# H_BRIGGE_1.net
KiCad netlist of a schematic drawn in Altium Designer
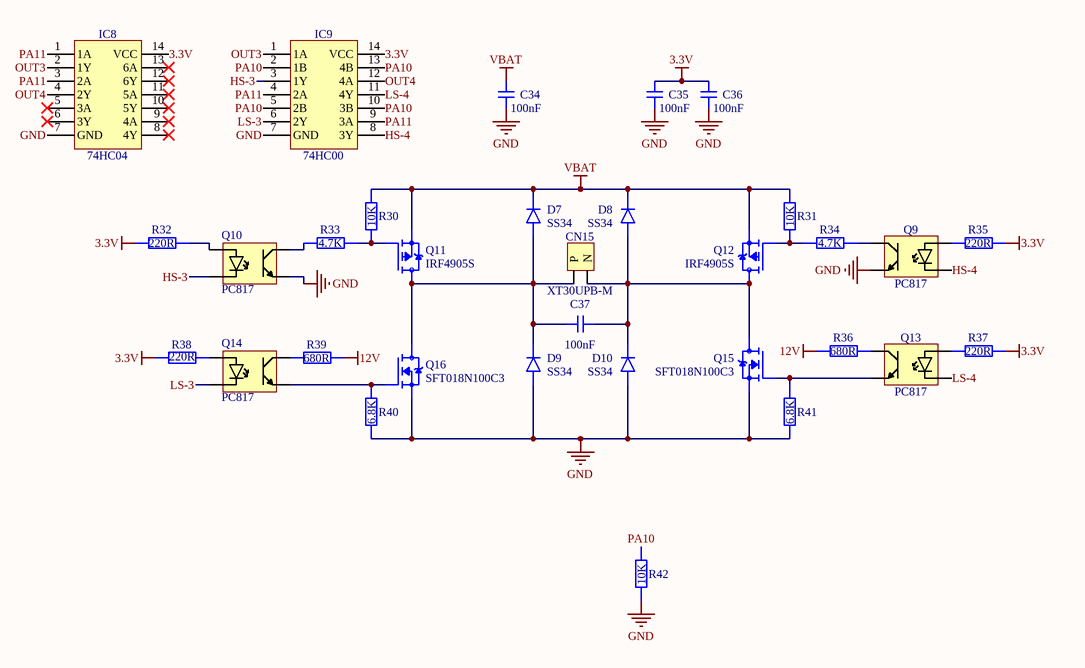
[diagram p0: H_BRIGGE_1.SchDoc]

(export (version "E")
  (design (tool "Eeschema 10.0.6"))
  (components
    (comp (ref "C34")
      (value "100nF")
      (footprint "CAP-0603-2")
      (description "100nF ±10% 50V Ceramic Capacitor X7R 0603")
      (fields (field (name "MANUFACTURER") "Samsung Electro-Mechanics") (field (name "LCSC PART #") "C1591"))
      (libsource (lib "CbyP") (part "CL10B104KB8NNNC"))
    )
    (comp (ref "C35")
      (value "100nF")
      (footprint "CAP-0603-2")
      (description "100nF ±10% 50V Ceramic Capacitor X7R 0603")
      (fields (field (name "MANUFACTURER") "Samsung Electro-Mechanics") (field (name "LCSC PART #") "C1591"))
      (libsource (lib "CbyP") (part "CL10B104KB8NNNC"))
    )
    (comp (ref "C36")
      (value "100nF")
      (footprint "CAP-0603-2")
      (description "100nF ±10% 50V Ceramic Capacitor X7R 0603")
      (fields (field (name "MANUFACTURER") "Samsung Electro-Mechanics") (field (name "LCSC PART #") "C1591"))
      (libsource (lib "CbyP") (part "CL10B104KB8NNNC"))
    )
    (comp (ref "C37")
      (value "100nF")
      (footprint "CAP-0603-2")
      (description "100nF ±10% 50V Ceramic Capacitor X7R 0603")
      (fields (field (name "MANUFACTURER") "Samsung Electro-Mechanics") (field (name "LCSC PART #") "C1591"))
      (libsource (lib "CbyP") (part "CL10B104KB8NNNC"))
    )
    (comp (ref "CN15")
      (value "XT30UPB-M")
      (footprint "XT30UPB-M")
      (description "Banana and Tip Connector Adapters")
      (fields
        (field (name "MANUFACTURER") "Changzhou Amass Elec")
        (field (name "MFR.PART #") "XT30PW-M30.G.Y")
      )
      (libsource (lib "CbyP") (part "XT30UPB-M"))
    )
    (comp (ref "D7")
      (value "SS34")
      (footprint "SMA(DO-214AC)")
      (description "Diode Independent 40V 3A Surface Mount SMA(DO-214AC)")
      (fields (field (name "MANUFACTURER") "GOODWORK") (field (name "LCSC PART #") "C908680"))
      (libsource (lib "CbyP") (part "SS34"))
    )
    (comp (ref "D8")
      (value "SS34")
      (footprint "SMA(DO-214AC)")
      (description "Diode Independent 40V 3A Surface Mount SMA(DO-214AC)")
      (fields (field (name "MANUFACTURER") "GOODWORK") (field (name "LCSC PART #") "C908680"))
      (libsource (lib "CbyP") (part "SS34"))
    )
    (comp (ref "D9")
      (value "SS34")
      (footprint "SMA(DO-214AC)")
      (description "Diode Independent 40V 3A Surface Mount SMA(DO-214AC)")
      (fields (field (name "MANUFACTURER") "GOODWORK") (field (name "LCSC PART #") "C908680"))
      (libsource (lib "CbyP") (part "SS34"))
    )
    (comp (ref "D10")
      (value "SS34")
      (footprint "SMA(DO-214AC)")
      (description "Diode Independent 40V 3A Surface Mount SMA(DO-214AC)")
      (fields (field (name "MANUFACTURER") "GOODWORK") (field (name "LCSC PART #") "C908680"))
      (libsource (lib "CbyP") (part "SS34"))
    )
    (comp (ref "IC8")
      (value "74HC04")
      (footprint "SOP-14")
      (description "2V~6V 16ns@6V,50pF 2uA 6 1 SOIC-14 Gates and Inverters RoHS")
      (fields (field (name "MANUFACTURER") "TI") (field (name "MFR.PART #") "SN74HC04DR"))
      (libsource (lib "CbyP") (part "SN74HC04DR"))
    )
    (comp (ref "IC9")
      (value "74HC00")
      (footprint "SOP-14")
      (description "2uA 2V~6V 15ns@6V,50pF SOIC-14 Gates and Inverters RoHS")
      (fields (field (name "MANUFACTURER") "TI") (field (name "MFR.PART #") "SN74HC00DR"))
      (libsource (lib "CbyP") (part "SN74HC00DR"))
    )
    (comp (ref "Q9")
      (value "PC817")
      (footprint "SOP-4")
      (description "Phototransistor Output 5kVrms 1 Channel SOP-4-2.54mm")
      (fields (field (name "MANUFACTURER") "UMW") (field (name "MFR.PART #") "PC817C-S"))
      (libsource (lib "CbyP") (part "PC817C-S"))
    )
    (comp (ref "Q10")
      (value "PC817")
      (footprint "SOP-4")
      (description "Phototransistor Output 5kVrms 1 Channel SOP-4-2.54mm")
      (fields (field (name "MANUFACTURER") "UMW") (field (name "MFR.PART #") "PC817C-S"))
      (libsource (lib "XE_BIA") (part "PC817C-S"))
    )
    (comp (ref "Q11")
      (value "IRF4905S")
      (footprint "TO-263")
      (description "P-Channel 55V 70A 170W Surface Mount D2PAK")
      (fields (field (name "MANUFACTURER") "Infineon") (field (name "MFR.PART #") "IRF4905STRLPBF"))
      (libsource (lib "CbyP") (part "IRF4905STRLPBF"))
    )
    (comp (ref "Q12")
      (value "IRF4905S")
      (footprint "TO-263")
      (description "P-Channel 55V 70A 170W Surface Mount D2PAK")
      (fields (field (name "MANUFACTURER") "Infineon") (field (name "MFR.PART #") "IRF4905STRLPBF"))
      (libsource (lib "CbyP") (part "IRF4905STRLPBF"))
    )
    (comp (ref "Q13")
      (value "PC817")
      (footprint "SOP-4")
      (description "Phototransistor Output 5kVrms 1 Channel SOP-4-2.54mm")
      (fields (field (name "MANUFACTURER") "UMW") (field (name "MFR.PART #") "PC817C-S"))
      (libsource (lib "CbyP") (part "PC817C-S"))
    )
    (comp (ref "Q14")
      (value "PC817")
      (footprint "SOP-4")
      (description "Phototransistor Output 5kVrms 1 Channel SOP-4-2.54mm")
      (fields (field (name "MANUFACTURER") "UMW") (field (name "MFR.PART #") "PC817C-S"))
      (libsource (lib "XE_BIA") (part "PC817C-S"))
    )
    (comp (ref "Q15")
      (value "SFT018N100C3")
      (footprint "TOLL")
      (description "N-Channel 100V 320A 312W Surface Mount TOLL")
      (fields (field (name "MANUFACTURER") "SCILICON") (field (name "LCSC PART #") "C42395330"))
      (libsource (lib "CbyP") (part "SFT018N100C3"))
    )
    (comp (ref "Q16")
      (value "SFT018N100C3")
      (footprint "TOLL")
      (description "N-Channel 100V 320A 312W Surface Mount TOLL")
      (fields (field (name "MANUFACTURER") "SCILICON") (field (name "LCSC PART #") "C42395330"))
      (libsource (lib "CbyP") (part "SFT018N100C3"))
    )
    (comp (ref "R30")
      (value "10K")
      (footprint "RES-0603-1")
      (description "100mW 10kΩ 75V Thick Film Resistor ±100ppm/℃ ±1% 0603 Chip Resistor - Surface Mount RoHS")
      (fields (field (name "MANUFACTURER") "YAGEO") (field (name "LCSC PART #") "C98220"))
      (libsource (lib "CbyP") (part "RC0603FR-0710KL"))
    )
    (comp (ref "R31")
      (value "10K")
      (footprint "RES-0603-1")
      (description "100mW 10kΩ 75V Thick Film Resistor ±100ppm/℃ ±1% 0603 Chip Resistor - Surface Mount RoHS")
      (fields (field (name "MANUFACTURER") "YAGEO") (field (name "LCSC PART #") "C98220"))
      (libsource (lib "CbyP") (part "RC0603FR-0710KL"))
    )
    (comp (ref "R32")
      (value "220R")
      (footprint "RES-0603-1")
      (description "220Ω ±1% 100mW 0603 Thick Film Resistor")
      (fields (field (name "MANUFACTURER") "UNI-ROYAL") (field (name "MFR.PART #") "0603WAF2200T5E"))
      (libsource (lib "CbyP") (part "0603WAF2200T5E"))
    )
    (comp (ref "R33")
      (value "4.7K")
      (footprint "RES-0603-1")
      (description "100mW 4.7kΩ 75V Thick Film Resistor ±100ppm/℃ ±1% 0603 Chip Resistor - Surface Mount RoHS")
      (fields (field (name "MANUFACTURER") "YAGEO") (field (name "MFR.PART #") "RC0603FR-074K7L"))
      (libsource (lib "CbyP") (part "RC0603FR-074K7L"))
    )
    (comp (ref "R34")
      (value "4.7K")
      (footprint "RES-0603-1")
      (description "100mW 4.7kΩ 75V Thick Film Resistor ±100ppm/℃ ±1% 0603 Chip Resistor - Surface Mount RoHS")
      (fields (field (name "MANUFACTURER") "YAGEO") (field (name "MFR.PART #") "RC0603FR-074K7L"))
      (libsource (lib "CbyP") (part "RC0603FR-074K7L"))
    )
    (comp (ref "R35")
      (value "220R")
      (footprint "RES-0603-1")
      (description "220Ω ±1% 100mW 0603 Thick Film Resistor")
      (fields (field (name "MANUFACTURER") "UNI-ROYAL") (field (name "MFR.PART #") "0603WAF2200T5E"))
      (libsource (lib "CbyP") (part "0603WAF2200T5E"))
    )
    (comp (ref "R36")
      (value "680R")
      (footprint "RES-0603-1")
      (description "680Ω ±1% 100mW 0603 Thick Film Resistor")
      (fields (field (name "MANUFACTURER") "FOJAN") (field (name "MFR.PART #") "FRC0603F6800TS"))
      (libsource (lib "CbyP") (part "FRC0603F6800TS"))
    )
    (comp (ref "R37")
      (value "220R")
      (footprint "RES-0603-1")
      (description "220Ω ±1% 100mW 0603 Thick Film Resistor")
      (fields (field (name "MANUFACTURER") "UNI-ROYAL") (field (name "MFR.PART #") "0603WAF2200T5E"))
      (libsource (lib "CbyP") (part "0603WAF2200T5E"))
    )
    (comp (ref "R38")
      (value "220R")
      (footprint "RES-0603-1")
      (description "220Ω ±1% 100mW 0603 Thick Film Resistor")
      (fields (field (name "MANUFACTURER") "UNI-ROYAL") (field (name "MFR.PART #") "0603WAF2200T5E"))
      (libsource (lib "CbyP") (part "0603WAF2200T5E"))
    )
    (comp (ref "R39")
      (value "680R")
      (footprint "RES-0603-1")
      (description "680Ω ±1% 100mW 0603 Thick Film Resistor")
      (fields (field (name "MANUFACTURER") "FOJAN") (field (name "MFR.PART #") "FRC0603F6800TS"))
      (libsource (lib "CbyP") (part "FRC0603F6800TS"))
    )
    (comp (ref "R40")
      (value "6.8K")
      (footprint "RES-0603-1")
      (description "6.8kΩ ±1% 100mW 0603 Thick Film Resistor")
      (fields (field (name "MANUFACTURER") "UNI-ROYAL") (field (name "MFR.PART #") "0603WAF6801T5E"))
      (libsource (lib "CbyP") (part "0603WAF6801T5E"))
    )
    (comp (ref "R41")
      (value "6.8K")
      (footprint "RES-0603-1")
      (description "6.8kΩ ±1% 100mW 0603 Thick Film Resistor")
      (fields (field (name "MANUFACTURER") "UNI-ROYAL") (field (name "MFR.PART #") "0603WAF6801T5E"))
      (libsource (lib "CbyP") (part "0603WAF6801T5E"))
    )
    (comp (ref "R42")
      (value "10K")
      (footprint "RES-0603-1")
      (description "100mW 10kΩ 75V Thick Film Resistor ±100ppm/℃ ±1% 0603 Chip Resistor - Surface Mount RoHS")
      (fields (field (name "MANUFACTURER") "YAGEO") (field (name "LCSC PART #") "C98220"))
      (libsource (lib "CbyP") (part "RC0603FR-0710KL"))
    )
  )
  (nets
    (net (code "1") (name "/HS-3") (class "Default")
      (node (ref "IC9") (pin "3") (pinfunction "1Y_3") (pintype "passive"))
      (node (ref "Q10") (pin "2") (pinfunction "K_2") (pintype "passive"))
    )
    (net (code "2") (name "/HS-4") (class "Default")
      (node (ref "IC9") (pin "8") (pinfunction "3Y_8") (pintype "passive"))
      (node (ref "Q9") (pin "2") (pinfunction "K_2") (pintype "passive"))
    )
    (net (code "3") (name "/LS-3") (class "Default")
      (node (ref "IC9") (pin "6") (pinfunction "2Y_6") (pintype "passive"))
      (node (ref "Q14") (pin "2") (pinfunction "K_2") (pintype "passive"))
    )
    (net (code "4") (name "/LS-4") (class "Default")
      (node (ref "IC9") (pin "11") (pinfunction "4Y_11") (pintype "passive"))
      (node (ref "Q13") (pin "2") (pinfunction "K_2") (pintype "passive"))
    )
    (net (code "5") (name "/OUT3") (class "Default")
      (node (ref "IC8") (pin "2") (pinfunction "1Y_2") (pintype "passive"))
      (node (ref "IC9") (pin "1") (pinfunction "1A_1") (pintype "passive"))
    )
    (net (code "6") (name "/OUT4") (class "Default")
      (node (ref "IC8") (pin "4") (pinfunction "2Y_4") (pintype "passive"))
      (node (ref "IC9") (pin "12") (pinfunction "4A_12") (pintype "passive"))
    )
    (net (code "7") (name "/PA10") (class "Default")
      (node (ref "IC9") (pin "10") (pinfunction "3B_10") (pintype "passive"))
      (node (ref "IC9") (pin "13") (pinfunction "4B_13") (pintype "passive"))
      (node (ref "IC9") (pin "2") (pinfunction "1B_2") (pintype "passive"))
      (node (ref "IC9") (pin "5") (pinfunction "2B_5") (pintype "passive"))
      (node (ref "R42") (pin "2") (pinfunction "2_2") (pintype "passive"))
    )
    (net (code "8") (name "/PA11") (class "Default")
      (node (ref "IC8") (pin "1") (pinfunction "1A_1") (pintype "passive"))
      (node (ref "IC8") (pin "3") (pinfunction "2A_3") (pintype "passive"))
      (node (ref "IC9") (pin "4") (pinfunction "2A_4") (pintype "passive"))
      (node (ref "IC9") (pin "9") (pinfunction "3A_9") (pintype "passive"))
    )
    (net (code "9") (name "3.3V") (class "Default")
      (node (ref "C35") (pin "1") (pinfunction "1_1") (pintype "passive"))
      (node (ref "C36") (pin "1") (pinfunction "1_1") (pintype "passive"))
      (node (ref "IC8") (pin "14") (pinfunction "VCC_14") (pintype "passive"))
      (node (ref "IC9") (pin "14") (pinfunction "VCC_14") (pintype "passive"))
      (node (ref "R32") (pin "2") (pinfunction "2_2") (pintype "passive"))
      (node (ref "R35") (pin "1") (pinfunction "1_1") (pintype "passive"))
      (node (ref "R37") (pin "1") (pinfunction "1_1") (pintype "passive"))
      (node (ref "R38") (pin "2") (pinfunction "2_2") (pintype "passive"))
    )
    (net (code "10") (name "12V") (class "Default")
      (node (ref "R36") (pin "2") (pinfunction "2_2") (pintype "passive"))
      (node (ref "R39") (pin "2") (pinfunction "2_2") (pintype "passive"))
    )
    (net (code "11") (name "GND") (class "Default")
      (node (ref "C34") (pin "2") (pinfunction "2_2") (pintype "passive"))
      (node (ref "C35") (pin "2") (pinfunction "2_2") (pintype "passive"))
      (node (ref "C36") (pin "2") (pinfunction "2_2") (pintype "passive"))
      (node (ref "D10") (pin "1") (pinfunction "A_1") (pintype "passive"))
      (node (ref "D9") (pin "1") (pinfunction "A_1") (pintype "passive"))
      (node (ref "IC8") (pin "7") (pinfunction "GND_7") (pintype "passive"))
      (node (ref "IC9") (pin "7") (pinfunction "GND_7") (pintype "passive"))
      (node (ref "Q10") (pin "3") (pinfunction "E_3") (pintype "passive"))
      (node (ref "Q15") (pin "2") (pinfunction "S_2") (pintype "passive"))
      (node (ref "Q16") (pin "2") (pinfunction "S_2") (pintype "passive"))
      (node (ref "Q9") (pin "3") (pinfunction "E_3") (pintype "passive"))
      (node (ref "R40") (pin "1") (pinfunction "1_1") (pintype "passive"))
      (node (ref "R41") (pin "1") (pinfunction "1_1") (pintype "passive"))
      (node (ref "R42") (pin "1") (pinfunction "1_1") (pintype "passive"))
    )
    (net (code "12") (name "Net-(CN15-N)") (class "Default")
      (node (ref "C37") (pin "1") (pinfunction "1_1") (pintype "passive"))
      (node (ref "CN15") (pin "2") (pinfunction "N_2") (pintype "passive"))
      (node (ref "D10") (pin "2") (pinfunction "K_2") (pintype "passive"))
      (node (ref "D8") (pin "1") (pinfunction "A_1") (pintype "passive"))
      (node (ref "Q12") (pin "2") (pinfunction "D_2") (pintype "passive"))
      (node (ref "Q15") (pin "3") (pinfunction "D_3") (pintype "passive"))
    )
    (net (code "13") (name "Net-(CN15-P)") (class "Default")
      (node (ref "C37") (pin "2") (pinfunction "2_2") (pintype "passive"))
      (node (ref "CN15") (pin "1") (pinfunction "P_1") (pintype "passive"))
      (node (ref "D7") (pin "1") (pinfunction "A_1") (pintype "passive"))
      (node (ref "D9") (pin "2") (pinfunction "K_2") (pintype "passive"))
      (node (ref "Q11") (pin "2") (pinfunction "D_2") (pintype "passive"))
      (node (ref "Q16") (pin "3") (pinfunction "D_3") (pintype "passive"))
    )
    (net (code "14") (name "Net-(Q9-A)") (class "Default")
      (node (ref "Q9") (pin "1") (pinfunction "A_1") (pintype "passive"))
      (node (ref "R35") (pin "2") (pinfunction "2_2") (pintype "passive"))
    )
    (net (code "15") (name "Net-(Q9-C)") (class "Default")
      (node (ref "Q9") (pin "4") (pinfunction "C_4") (pintype "passive"))
      (node (ref "R34") (pin "2") (pinfunction "2_2") (pintype "passive"))
    )
    (net (code "16") (name "Net-(Q10-A)") (class "Default")
      (node (ref "Q10") (pin "1") (pinfunction "A_1") (pintype "passive"))
      (node (ref "R32") (pin "1") (pinfunction "1_1") (pintype "passive"))
    )
    (net (code "17") (name "Net-(Q10-C)") (class "Default")
      (node (ref "Q10") (pin "4") (pinfunction "C_4") (pintype "passive"))
      (node (ref "R33") (pin "1") (pinfunction "1_1") (pintype "passive"))
    )
    (net (code "18") (name "Net-(Q11-G)") (class "Default")
      (node (ref "Q11") (pin "1") (pinfunction "G_1") (pintype "passive"))
      (node (ref "R30") (pin "1") (pinfunction "1_1") (pintype "passive"))
      (node (ref "R33") (pin "2") (pinfunction "2_2") (pintype "passive"))
    )
    (net (code "19") (name "Net-(Q12-G)") (class "Default")
      (node (ref "Q12") (pin "1") (pinfunction "G_1") (pintype "passive"))
      (node (ref "R31") (pin "1") (pinfunction "1_1") (pintype "passive"))
      (node (ref "R34") (pin "1") (pinfunction "1_1") (pintype "passive"))
    )
    (net (code "20") (name "Net-(Q13-A)") (class "Default")
      (node (ref "Q13") (pin "1") (pinfunction "A_1") (pintype "passive"))
      (node (ref "R37") (pin "2") (pinfunction "2_2") (pintype "passive"))
    )
    (net (code "21") (name "Net-(Q13-C)") (class "Default")
      (node (ref "Q13") (pin "4") (pinfunction "C_4") (pintype "passive"))
      (node (ref "R36") (pin "1") (pinfunction "1_1") (pintype "passive"))
    )
    (net (code "22") (name "Net-(Q13-E)") (class "Default")
      (node (ref "Q13") (pin "3") (pinfunction "E_3") (pintype "passive"))
      (node (ref "Q15") (pin "1") (pinfunction "G_1") (pintype "passive"))
      (node (ref "R41") (pin "2") (pinfunction "2_2") (pintype "passive"))
    )
    (net (code "23") (name "Net-(Q14-A)") (class "Default")
      (node (ref "Q14") (pin "1") (pinfunction "A_1") (pintype "passive"))
      (node (ref "R38") (pin "1") (pinfunction "1_1") (pintype "passive"))
    )
    (net (code "24") (name "Net-(Q14-C)") (class "Default")
      (node (ref "Q14") (pin "4") (pinfunction "C_4") (pintype "passive"))
      (node (ref "R39") (pin "1") (pinfunction "1_1") (pintype "passive"))
    )
    (net (code "25") (name "Net-(Q14-E)") (class "Default")
      (node (ref "Q14") (pin "3") (pinfunction "E_3") (pintype "passive"))
      (node (ref "Q16") (pin "1") (pinfunction "G_1") (pintype "passive"))
      (node (ref "R40") (pin "2") (pinfunction "2_2") (pintype "passive"))
    )
    (net (code "26") (name "VBAT") (class "Default")
      (node (ref "C34") (pin "1") (pinfunction "1_1") (pintype "passive"))
      (node (ref "D7") (pin "2") (pinfunction "K_2") (pintype "passive"))
      (node (ref "D8") (pin "2") (pinfunction "K_2") (pintype "passive"))
      (node (ref "Q11") (pin "3") (pinfunction "S_3") (pintype "passive"))
      (node (ref "Q12") (pin "3") (pinfunction "S_3") (pintype "passive"))
      (node (ref "R30") (pin "2") (pinfunction "2_2") (pintype "passive"))
      (node (ref "R31") (pin "2") (pinfunction "2_2") (pintype "passive"))
    )
    (net (code "27") (name "unconnected-(IC8-3A-Pad5)") (class "Default")
      (node (ref "IC8") (pin "5") (pinfunction "3A_5") (pintype "passive+no_connect"))
    )
    (net (code "28") (name "unconnected-(IC8-3Y-Pad6)") (class "Default")
      (node (ref "IC8") (pin "6") (pinfunction "3Y_6") (pintype "passive+no_connect"))
    )
    (net (code "29") (name "unconnected-(IC8-4A-Pad9)") (class "Default")
      (node (ref "IC8") (pin "9") (pinfunction "4A_9") (pintype "passive+no_connect"))
    )
    (net (code "30") (name "unconnected-(IC8-4Y-Pad8)") (class "Default")
      (node (ref "IC8") (pin "8") (pinfunction "4Y_8") (pintype "passive+no_connect"))
    )
    (net (code "31") (name "unconnected-(IC8-5A-Pad11)") (class "Default")
      (node (ref "IC8") (pin "11") (pinfunction "5A_11") (pintype "passive+no_connect"))
    )
    (net (code "32") (name "unconnected-(IC8-5Y-Pad10)") (class "Default")
      (node (ref "IC8") (pin "10") (pinfunction "5Y_10") (pintype "passive+no_connect"))
    )
    (net (code "33") (name "unconnected-(IC8-6A-Pad13)") (class "Default")
      (node (ref "IC8") (pin "13") (pinfunction "6A_13") (pintype "passive+no_connect"))
    )
    (net (code "34") (name "unconnected-(IC8-6Y-Pad12)") (class "Default")
      (node (ref "IC8") (pin "12") (pinfunction "6Y_12") (pintype "passive+no_connect"))
    )
  )
)
